# pc.net
KiCad netlist of a schematic drawn in EAGLE
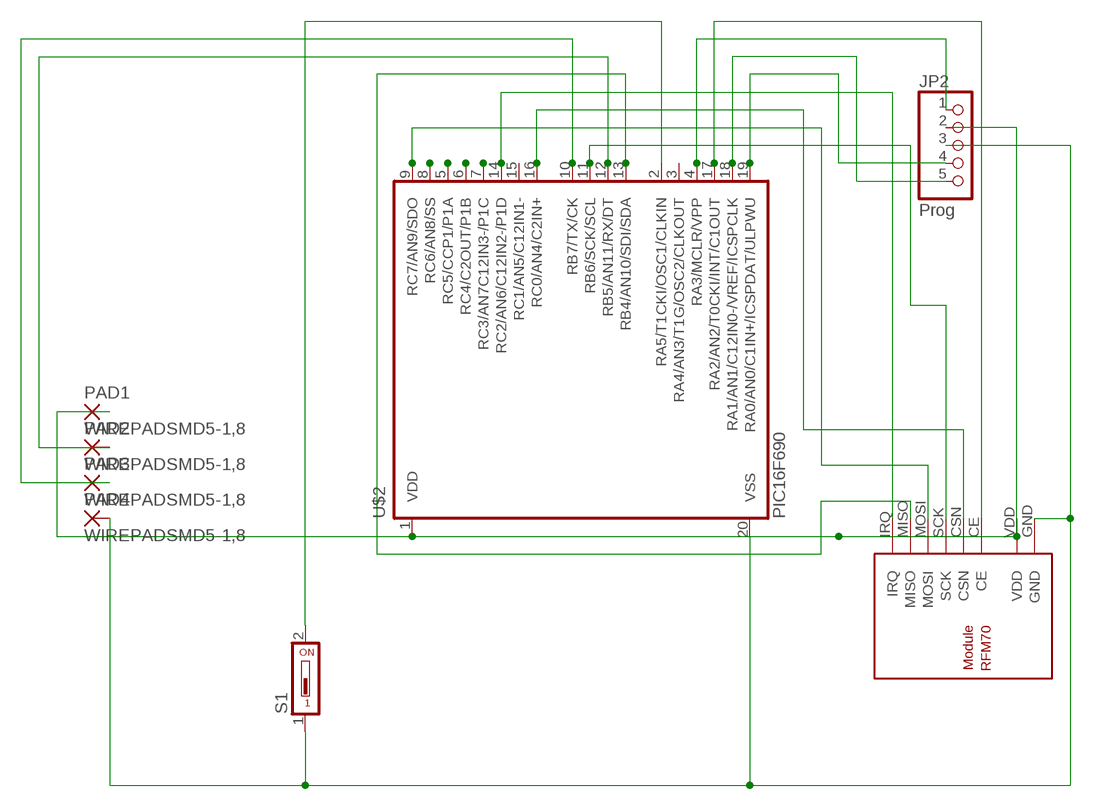
[diagram p0: schematic, sheet 1]

(export (version "E")
  (design (tool "Eeschema 10.0.6"))
  (components
    (comp (ref "JP2")
      (value "Prog")
      (footprint "eagle-import:1X05")
      (libsource (lib "eagle-import") (part "PINHD-1X5"))
    )
    (comp (ref "PAD1")
      (value "WIREPADSMD5-1,8")
      (footprint "eagle-import:5-1,8")
      (libsource (lib "eagle-import") (part "WIREPADSMD5-1,8"))
    )
    (comp (ref "PAD2")
      (value "WIREPADSMD5-1,8")
      (footprint "eagle-import:5-1,8")
      (libsource (lib "eagle-import") (part "WIREPADSMD5-1,8"))
    )
    (comp (ref "PAD3")
      (value "WIREPADSMD5-1,8")
      (footprint "eagle-import:5-1,8")
      (libsource (lib "eagle-import") (part "WIREPADSMD5-1,8"))
    )
    (comp (ref "PAD4")
      (value "WIREPADSMD5-1,8")
      (footprint "eagle-import:5-1,8")
      (libsource (lib "eagle-import") (part "WIREPADSMD5-1,8"))
    )
    (comp (ref "S1")
      (value "SD4-01")
      (footprint "eagle-import:SD4-01")
      (libsource (lib "eagle-import") (part "SD4-01"))
    )
    (comp (ref "U$1")
      (value "RFM70")
      (footprint "eagle-import:RFM70")
      (libsource (lib "eagle-import") (part "RFM70"))
    )
    (comp (ref "U$2")
      (value "PIC16F690")
      (footprint "eagle-import:SSOP20")
      (libsource (lib "eagle-import") (part "PIC16F690"))
    )
  )
  (nets
    (net (code "1") (name "Net-(PAD1-P)") (class "Default")
      (node (ref "JP2") (pin "2") (pinfunction "2_2") (pintype "passive"))
      (node (ref "PAD1") (pin "1") (pinfunction "P_1") (pintype "passive"))
      (node (ref "U$1") (pin "VDD") (pinfunction "VDD_VDD") (pintype "power_in"))
      (node (ref "U$2") (pin "1") (pinfunction "VDD_1") (pintype "power_in"))
    )
    (net (code "2") (name "Net-(PAD2-P)") (class "Default")
      (node (ref "PAD2") (pin "1") (pinfunction "P_1") (pintype "passive"))
      (node (ref "U$2") (pin "12") (pinfunction "RB5/AN11/RX/DT_12") (pintype "bidirectional"))
    )
    (net (code "3") (name "Net-(PAD3-P)") (class "Default")
      (node (ref "PAD3") (pin "1") (pinfunction "P_1") (pintype "passive"))
      (node (ref "U$2") (pin "10") (pinfunction "RB7/TX/CK_10") (pintype "bidirectional"))
    )
    (net (code "4") (name "Net-(PAD4-P)") (class "Default")
      (node (ref "JP2") (pin "3") (pinfunction "3_3") (pintype "passive"))
      (node (ref "PAD4") (pin "1") (pinfunction "P_1") (pintype "passive"))
      (node (ref "S1") (pin "1") (pinfunction "1_1") (pintype "passive"))
      (node (ref "U$1") (pin "GND") (pinfunction "GND_GND") (pintype "power_in"))
      (node (ref "U$2") (pin "20") (pinfunction "VSS_20") (pintype "power_in"))
    )
    (net (code "5") (name "Net-(U$2-RA0{slash}AN0{slash}C1IN+{slash}ICSPDAT{slash}ULPWU)") (class "Default")
      (node (ref "JP2") (pin "4") (pinfunction "4_4") (pintype "passive"))
      (node (ref "U$2") (pin "19") (pinfunction "RA0/AN0/C1IN+/ICSPDAT/ULPWU_19") (pintype "bidirectional"))
    )
    (net (code "6") (name "Net-(U$2-RA1{slash}AN1{slash}C12IN0-{slash}VREF{slash}ICSPCLK)") (class "Default")
      (node (ref "JP2") (pin "5") (pinfunction "5_5") (pintype "passive"))
      (node (ref "U$2") (pin "18") (pinfunction "RA1/AN1/C12IN0-/VREF/ICSPCLK_18") (pintype "bidirectional"))
    )
    (net (code "7") (name "Net-(U$2-RA2{slash}AN2{slash}T0CKI{slash}INT{slash}C1OUT)") (class "Default")
      (node (ref "U$1") (pin "CE") (pinfunction "CE_CE") (pintype "bidirectional"))
      (node (ref "U$2") (pin "17") (pinfunction "RA2/AN2/T0CKI/INT/C1OUT_17") (pintype "bidirectional"))
    )
    (net (code "8") (name "Net-(U$2-RA3{slash}MCLR{slash}VPP)") (class "Default")
      (node (ref "JP2") (pin "1") (pinfunction "1_1") (pintype "passive"))
      (node (ref "U$2") (pin "4") (pinfunction "RA3/MCLR/VPP_4") (pintype "bidirectional"))
    )
    (net (code "9") (name "Net-(U$2-RA5{slash}T1CKI{slash}OSC1{slash}CLKIN)") (class "Default")
      (node (ref "S1") (pin "2") (pinfunction "2_2") (pintype "passive"))
      (node (ref "U$2") (pin "2") (pinfunction "RA5/T1CKI/OSC1/CLKIN_2") (pintype "bidirectional"))
    )
    (net (code "10") (name "Net-(U$2-RB4{slash}AN10{slash}SDI{slash}SDA)") (class "Default")
      (node (ref "U$1") (pin "MISO") (pinfunction "MISO_MISO") (pintype "bidirectional"))
      (node (ref "U$2") (pin "13") (pinfunction "RB4/AN10/SDI/SDA_13") (pintype "bidirectional"))
    )
    (net (code "11") (name "Net-(U$2-RB6{slash}SCK{slash}SCL)") (class "Default")
      (node (ref "U$1") (pin "SCK") (pinfunction "SCK_SCK") (pintype "bidirectional"))
      (node (ref "U$2") (pin "11") (pinfunction "RB6/SCK/SCL_11") (pintype "bidirectional"))
    )
    (net (code "12") (name "Net-(U$2-RC0{slash}AN4{slash}C2IN+)") (class "Default")
      (node (ref "U$1") (pin "CSN") (pinfunction "CSN_CSN") (pintype "bidirectional"))
      (node (ref "U$2") (pin "16") (pinfunction "RC0/AN4/C2IN+_16") (pintype "bidirectional"))
    )
    (net (code "13") (name "Net-(U$2-RC2{slash}AN6{slash}C12IN2-{slash}P1D)") (class "Default")
      (node (ref "U$1") (pin "IRQ") (pinfunction "IRQ_IRQ") (pintype "bidirectional"))
      (node (ref "U$2") (pin "14") (pinfunction "RC2/AN6/C12IN2-/P1D_14") (pintype "bidirectional"))
    )
    (net (code "14") (name "Net-(U$2-RC7{slash}AN9{slash}SDO)") (class "Default")
      (node (ref "U$1") (pin "MOSI") (pinfunction "MOSI_MOSI") (pintype "bidirectional"))
      (node (ref "U$2") (pin "9") (pinfunction "RC7/AN9/SDO_9") (pintype "bidirectional"))
    )
    (net (code "15") (name "unconnected-(U$2-RA4{slash}AN3{slash}T1G{slash}OSC2{slash}CLKOUT-Pad3)") (class "Default")
      (node (ref "U$2") (pin "3") (pinfunction "RA4/AN3/T1G/OSC2/CLKOUT_3") (pintype "bidirectional"))
    )
    (net (code "16") (name "unconnected-(U$2-RC1{slash}AN5{slash}C12IN1--Pad15)") (class "Default")
      (node (ref "U$2") (pin "15") (pinfunction "RC1/AN5/C12IN1-_15") (pintype "bidirectional"))
    )
    (net (code "17") (name "unconnected-(U$2-RC3{slash}AN7C12IN3-{slash}P1C-Pad7)") (class "Default")
      (node (ref "U$2") (pin "7") (pinfunction "RC3/AN7C12IN3-/P1C_7") (pintype "bidirectional"))
    )
    (net (code "18") (name "unconnected-(U$2-RC4{slash}C2OUT{slash}P1B-Pad6)") (class "Default")
      (node (ref "U$2") (pin "6") (pinfunction "RC4/C2OUT/P1B_6") (pintype "bidirectional"))
    )
    (net (code "19") (name "unconnected-(U$2-RC5{slash}CCP1{slash}P1A-Pad5)") (class "Default")
      (node (ref "U$2") (pin "5") (pinfunction "RC5/CCP1/P1A_5") (pintype "bidirectional"))
    )
    (net (code "20") (name "unconnected-(U$2-RC6{slash}AN8{slash}SS-Pad8)") (class "Default")
      (node (ref "U$2") (pin "8") (pinfunction "RC6/AN8/SS_8") (pintype "bidirectional"))
    )
  )
)
